# 8_0.net
KiCad netlist of a schematic drawn in Altium Designer
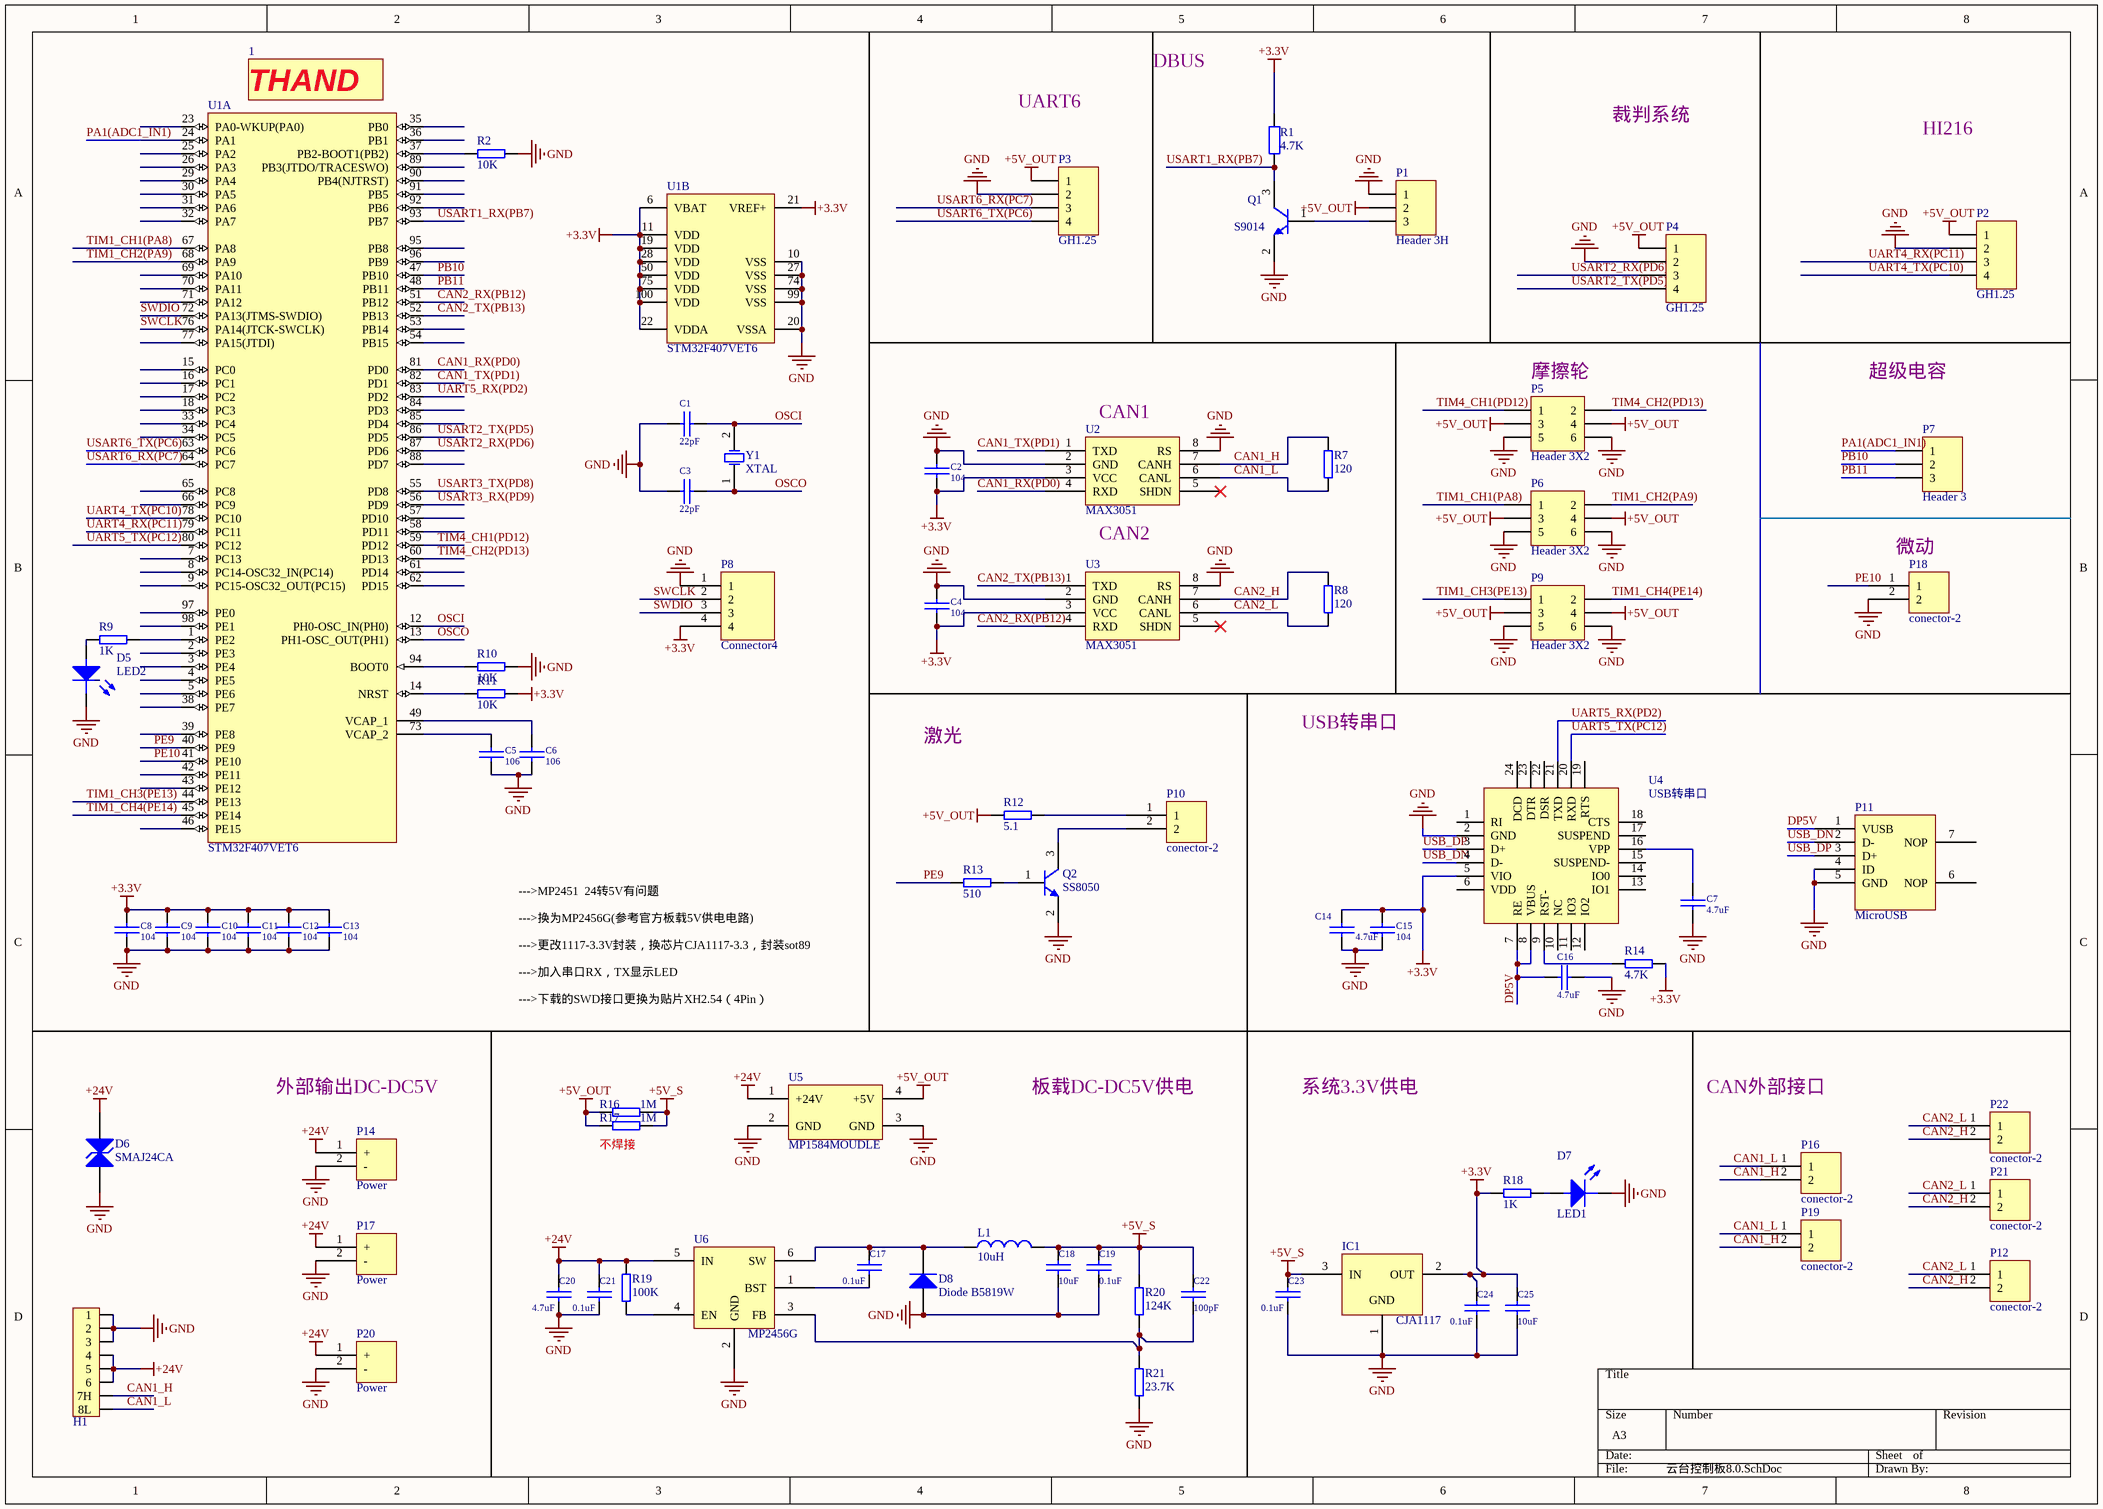
[diagram p0: 云台控制板8.0.SchDoc]

(export (version "E")
  (design (tool "Eeschema 10.0.6"))
  (components
    (comp (ref "1")
      (value "~")
      (footprint "THAND")
      (libsource (lib "G's Integrated_Library-System") (part "THAND"))
    )
    (comp (ref "C1")
      (value "22pF")
      (footprint "0805C")
      (description "Capacitor")
      (libsource (lib "Components") (part "CAP1"))
    )
    (comp (ref "C2")
      (value "104")
      (footprint "0805C")
      (description "Capacitor")
      (libsource (lib "Components") (part "CAP1"))
    )
    (comp (ref "C3")
      (value "22pF")
      (footprint "0805C")
      (description "Capacitor")
      (libsource (lib "Components") (part "CAP1"))
    )
    (comp (ref "C4")
      (value "104")
      (footprint "0805C")
      (description "Capacitor")
      (libsource (lib "Components") (part "CAP1"))
    )
    (comp (ref "C5")
      (value "106")
      (footprint "0805C")
      (description "Capacitor")
      (libsource (lib "Components") (part "CAP1"))
    )
    (comp (ref "C6")
      (value "106")
      (footprint "0805C")
      (description "Capacitor")
      (libsource (lib "Components") (part "CAP1"))
    )
    (comp (ref "C7")
      (value "4.7uF")
      (footprint "0805C")
      (description "Capacitor")
      (libsource (lib "Components") (part "CAP1"))
    )
    (comp (ref "C8")
      (value "104")
      (footprint "0805C")
      (description "Capacitor")
      (libsource (lib "Components") (part "CAP1"))
    )
    (comp (ref "C9")
      (value "104")
      (footprint "0805C")
      (description "Capacitor")
      (libsource (lib "Components") (part "CAP1"))
    )
    (comp (ref "C10")
      (value "104")
      (footprint "0805C")
      (description "Capacitor")
      (libsource (lib "Components") (part "CAP1"))
    )
    (comp (ref "C11")
      (value "104")
      (footprint "0805C")
      (description "Capacitor")
      (libsource (lib "Components") (part "CAP1"))
    )
    (comp (ref "C12")
      (value "104")
      (footprint "0805C")
      (description "Capacitor")
      (libsource (lib "Components") (part "CAP1"))
    )
    (comp (ref "C13")
      (value "104")
      (footprint "0805C")
      (description "Capacitor")
      (libsource (lib "Components") (part "CAP1"))
    )
    (comp (ref "C14")
      (value "4.7uF")
      (footprint "0805C")
      (description "Capacitor")
      (libsource (lib "Components") (part "CAP1"))
    )
    (comp (ref "C15")
      (value "104")
      (footprint "0805C")
      (description "Capacitor")
      (libsource (lib "Components") (part "CAP1"))
    )
    (comp (ref "C16")
      (value "4.7uF")
      (footprint "0805C")
      (description "Capacitor")
      (libsource (lib "Components") (part "CAP1"))
    )
    (comp (ref "C17")
      (value "0.1uF")
      (footprint "0805C")
      (description "Capacitor")
      (libsource (lib "Components") (part "CAP1"))
    )
    (comp (ref "C18")
      (value "10uF")
      (footprint "1206C")
      (description "Capacitor")
      (libsource (lib "Components") (part "CAP1"))
    )
    (comp (ref "C19")
      (value "0.1uF")
      (footprint "0805C")
      (description "Capacitor")
      (libsource (lib "Components") (part "CAP1"))
    )
    (comp (ref "C20")
      (value "4.7uF")
      (footprint "1206C")
      (description "Capacitor")
      (libsource (lib "Components") (part "CAP1"))
    )
    (comp (ref "C21")
      (value "0.1uF")
      (footprint "0805C")
      (description "Capacitor")
      (libsource (lib "Components") (part "CAP1"))
    )
    (comp (ref "C22")
      (value "100pF")
      (footprint "0805C")
      (description "Capacitor")
      (libsource (lib "Components") (part "CAP1"))
    )
    (comp (ref "C23")
      (value "0.1uF")
      (footprint "0805C")
      (description "Capacitor")
      (libsource (lib "Components") (part "CAP1"))
    )
    (comp (ref "C24")
      (value "0.1uF")
      (footprint "0805C")
      (description "Capacitor")
      (libsource (lib "Components") (part "CAP1"))
    )
    (comp (ref "C25")
      (value "10uF")
      (footprint "1206C")
      (description "Capacitor")
      (libsource (lib "Components") (part "CAP1"))
    )
    (comp (ref "D5")
      (value "LED2")
      (footprint "0805D")
      (description "Typical RED GaAs LED")
      (fields (field (name "PUBLISHER") "Altium Limited"))
      (libsource (lib "Components") (part "LED1"))
    )
    (comp (ref "D6")
      (value "SMAJ24CA")
      (footprint "SMA(DO-214AC)")
      (description "Diode TVS 双向")
      (fields (field (name "PUBLISHER") "Altium Limited"))
      (libsource (lib "Roxin_lib") (part "Diode TVS Bi"))
    )
    (comp (ref "D7")
      (value "LED1")
      (footprint "0805D")
      (description "Typical RED GaAs LED")
      (fields (field (name "PUBLISHER") "Altium Limited"))
      (libsource (lib "Components") (part "LED1"))
    )
    (comp (ref "D8")
      (value "Diode B5819W")
      (footprint "SOD-123")
      (description "1 Amp Fast Recovery Rectifier")
      (fields (field (name "PUBLISHER") "Altium Limited"))
      (libsource (lib "Roxin_lib") (part "Diode B5819W"))
    )
    (comp (ref "H1")
      (value "云台电机8P")
      (footprint "云台电机8P")
      (libsource (lib "IRS21867+SIR662DP") (part "云台电机8P"))
    )
    (comp (ref "IC1")
      (value "CJA1117")
      (footprint "SOT89 - duplicate")
      (libsource (lib "Roxin_lib") (part "CJA1117"))
    )
    (comp (ref "L1")
      (value "10uH")
      (footprint "SMDRH63")
      (description "Inductor")
      (fields (field (name "PUBLISHER") "Altium Limited"))
      (libsource (lib "Roxin_lib") (part "Inductor"))
    )
    (comp (ref "P1")
      (value "Header 3H")
      (footprint "HDR1X3H")
      (description "Header, 3-Pin, Right Angle")
      (fields (field (name "PUBLISHER") "Altium Limited"))
      (libsource (lib "Miscellaneous Connectors") (part "Header 3H"))
    )
    (comp (ref "P2")
      (value "GH1.25")
      (footprint "GH1.25_4P")
      (description "Header, 4-Pin")
      (fields (field (name "PUBLISHER") "Altium Limited"))
      (libsource (lib "主控V1") (part "Header 4"))
    )
    (comp (ref "P3")
      (value "GH1.25")
      (footprint "GH1.25_4P")
      (description "Header, 4-Pin")
      (fields (field (name "PUBLISHER") "Altium Limited"))
      (libsource (lib "主控V1") (part "Header 4"))
    )
    (comp (ref "P4")
      (value "GH1.25")
      (footprint "GH1.25_4P")
      (description "Header, 4-Pin")
      (fields (field (name "PUBLISHER") "Altium Limited"))
      (libsource (lib "主控V1") (part "Header 4"))
    )
    (comp (ref "P5")
      (value "Header 3X2")
      (footprint "HDR2X3")
      (description "Header, 3-Pin, Dual row")
      (fields (field (name "PUBLISHER") "Altium Limited"))
      (libsource (lib "Miscellaneous Connectors") (part "Header 3X2"))
    )
    (comp (ref "P6")
      (value "Header 3X2")
      (footprint "HDR2X3")
      (description "Header, 3-Pin, Dual row")
      (fields (field (name "PUBLISHER") "Altium Limited"))
      (libsource (lib "Miscellaneous Connectors") (part "Header 3X2"))
    )
    (comp (ref "P7")
      (value "Header 3")
      (footprint "HDR1X3")
      (description "Header, 3-Pin")
      (fields (field (name "PUBLISHER") "Altium Limited"))
      (libsource (lib "Miscellaneous Connectors") (part "Header 3"))
    )
    (comp (ref "P8")
      (value "Connector4")
      (footprint "XH2.54-4P")
      (description "白色插头母头")
      (libsource (lib "mylib") (part "Connector4"))
    )
    (comp (ref "P9")
      (value "Header 3X2")
      (footprint "HDR2X3")
      (description "Header, 3-Pin, Dual row")
      (fields (field (name "PUBLISHER") "Altium Limited"))
      (libsource (lib "Miscellaneous Connectors") (part "Header 3X2"))
    )
    (comp (ref "P10")
      (value "conector-2")
      (footprint "GH1.25-2P")
      (libsource (lib "Roxin_lib") (part "conector-2"))
    )
    (comp (ref "P11") (value "MicroUSB") (footprint "Micro-USB沉板") (libsource (lib "USB") (part "MicroUSB")))
    (comp (ref "P12")
      (value "conector-2")
      (footprint "GH1.25-2P")
      (libsource (lib "Roxin_lib") (part "conector-2"))
    )
    (comp (ref "P14") (value "Power") (footprint "XT30") (libsource (lib "云台控制板3.0") (part "Power")))
    (comp (ref "P16")
      (value "conector-2")
      (footprint "GH1.25-2P")
      (libsource (lib "Roxin_lib") (part "conector-2"))
    )
    (comp (ref "P17") (value "Power") (footprint "XT30") (libsource (lib "云台控制板3.0") (part "Power")))
    (comp (ref "P18")
      (value "conector-2")
      (footprint "GH1.25-2P")
      (libsource (lib "Roxin_lib") (part "conector-2"))
    )
    (comp (ref "P19")
      (value "conector-2")
      (footprint "GH1.25-2P")
      (libsource (lib "Roxin_lib") (part "conector-2"))
    )
    (comp (ref "P20") (value "Power") (footprint "XT30") (libsource (lib "Roxin_lib") (part "Power")))
    (comp (ref "P21")
      (value "conector-2")
      (footprint "GH1.25-2P")
      (libsource (lib "Roxin_lib") (part "conector-2"))
    )
    (comp (ref "P22")
      (value "conector-2")
      (footprint "GH1.25-2P")
      (libsource (lib "Roxin_lib") (part "conector-2"))
    )
    (comp (ref "Q1")
      (value "S9014")
      (footprint "SOT-23")
      (description "NPN贴片三极管")
      (fields (field (name "PUBLISHER") "Altium Limited"))
      (libsource (lib "主控V1") (part "SS8050"))
    )
    (comp (ref "Q2")
      (value "SS8050")
      (footprint "SOT-23")
      (description "NPN贴片三极管")
      (fields (field (name "PUBLISHER") "Altium Limited"))
      (libsource (lib "主控V1") (part "SS8050"))
    )
    (comp (ref "R1")
      (value "4.7K")
      (footprint "R0805")
      (description "Resistor")
      (fields (field (name "Comment") "Res2") (field (name "PUBLISHER") "Altium Limited"))
      (libsource (lib "Roxin_lib") (part "Res2"))
    )
    (comp (ref "R2")
      (value "10K")
      (footprint "0805R")
      (description "Resistance")
      (libsource (lib "Components") (part "RES"))
    )
    (comp (ref "R7")
      (value "120")
      (footprint "0805R")
      (description "Resistance")
      (libsource (lib "Components") (part "RES"))
    )
    (comp (ref "R8")
      (value "120")
      (footprint "0805R")
      (description "Resistance")
      (libsource (lib "Components") (part "RES"))
    )
    (comp (ref "R9")
      (value "1K")
      (footprint "0805R")
      (description "Resistance")
      (libsource (lib "Components") (part "RES"))
    )
    (comp (ref "R10")
      (value "10K")
      (footprint "0805R")
      (description "Resistance")
      (libsource (lib "Components") (part "RES"))
    )
    (comp (ref "R11")
      (value "10K")
      (footprint "0805R")
      (description "Resistance")
      (libsource (lib "Components") (part "RES"))
    )
    (comp (ref "R12")
      (value "5.1")
      (footprint "0805R")
      (description "Resistance")
      (libsource (lib "Components") (part "RES"))
    )
    (comp (ref "R13")
      (value "510")
      (footprint "0805R")
      (description "Resistance")
      (libsource (lib "Components") (part "RES"))
    )
    (comp (ref "R14")
      (value "4.7K")
      (footprint "0805R")
      (description "Resistance")
      (libsource (lib "Components") (part "RES"))
    )
    (comp (ref "R16")
      (value "1M")
      (footprint "0805R")
      (description "Resistance")
      (libsource (lib "Components") (part "RES"))
    )
    (comp (ref "R17")
      (value "1M")
      (footprint "0805R")
      (description "Resistance")
      (libsource (lib "Components") (part "RES"))
    )
    (comp (ref "R18")
      (value "1K")
      (footprint "0805R")
      (description "Resistance")
      (libsource (lib "Components") (part "RES"))
    )
    (comp (ref "R19")
      (value "100K")
      (footprint "0805R")
      (description "Resistance")
      (libsource (lib "Components") (part "RES"))
    )
    (comp (ref "R20")
      (value "124K")
      (footprint "0805R")
      (description "Resistance")
      (libsource (lib "Components") (part "RES"))
    )
    (comp (ref "R21")
      (value "23.7K")
      (footprint "0805R")
      (description "Resistance")
      (libsource (lib "Components") (part "RES"))
    )
    (comp (ref "U1")
      (value "STM32F407VET6")
      (footprint "STM-LQFP100_N")
      (fields (field (name "MANUFACTURER") "STMicroelectronics"))
      (libsource (lib "STMicroelectronics STM32 F4") (part "STM32F407VET6"))
    )
    (comp (ref "U2") (value "MAX3051") (footprint "SOIC8") (libsource (lib "PTZ") (part "MAX3051")))
    (comp (ref "U3") (value "MAX3051") (footprint "SOIC8") (libsource (lib "PTZ") (part "MAX3051")))
    (comp (ref "U4") (value "USB转串口") (footprint "CP2102") (libsource (lib "mylib") (part "CP2102")))
    (comp (ref "U5")
      (value "MP1584MOUDLE")
      (footprint "24-5VMP1584MOUDLE")
      (libsource (lib "Roxin_lib") (part "24-5VMP1584MOUDLE"))
    )
    (comp (ref "U6") (value "MP2456G") (footprint "SOT23-6") (libsource (lib "Roxin_lib") (part "MP2456G")))
    (comp (ref "Y1")
      (value "XTAL")
      (footprint "JZ")
      (description "Crystal Oscillator")
      (fields (field (name "PUBLISHER") "Altium Limited"))
      (libsource (lib "Roxin_lib") (part "XTAL"))
    )
  )
  (nets
    (net (code "1") (name "+3.3V") (class "Default")
      (node (ref "C10") (pin "1") (pinfunction "1_1") (pintype "passive"))
      (node (ref "C11") (pin "1") (pinfunction "1_1") (pintype "passive"))
      (node (ref "C12") (pin "1") (pinfunction "1_1") (pintype "passive"))
      (node (ref "C13") (pin "1") (pinfunction "1_1") (pintype "passive"))
      (node (ref "C14") (pin "1") (pinfunction "1_1") (pintype "passive"))
      (node (ref "C15") (pin "2") (pinfunction "2_2") (pintype "passive"))
      (node (ref "C2") (pin "2") (pinfunction "2_2") (pintype "passive"))
      (node (ref "C24") (pin "1") (pinfunction "1_1") (pintype "passive"))
      (node (ref "C25") (pin "1") (pinfunction "1_1") (pintype "passive"))
      (node (ref "C4") (pin "2") (pinfunction "2_2") (pintype "passive"))
      (node (ref "C8") (pin "1") (pinfunction "1_1") (pintype "passive"))
      (node (ref "C9") (pin "1") (pinfunction "1_1") (pintype "passive"))
      (node (ref "IC1") (pin "2") (pinfunction "OUT_2") (pintype "passive"))
      (node (ref "P8") (pin "4") (pinfunction "4_4") (pintype "passive"))
      (node (ref "R1") (pin "2") (pinfunction "2_2") (pintype "passive"))
      (node (ref "R11") (pin "2") (pinfunction "2_2") (pintype "passive"))
      (node (ref "R14") (pin "2") (pinfunction "2_2") (pintype "passive"))
      (node (ref "R18") (pin "1") (pinfunction "1_1") (pintype "passive"))
      (node (ref "U1") (pin "100") (pinfunction "VDD_100") (pintype "power_in"))
      (node (ref "U1") (pin "11") (pinfunction "VDD_11") (pintype "power_in"))
      (node (ref "U1") (pin "19") (pinfunction "VDD_19") (pintype "power_in"))
      (node (ref "U1") (pin "21") (pinfunction "VREF+_21") (pintype "power_in"))
      (node (ref "U1") (pin "22") (pinfunction "VDDA_22") (pintype "power_in"))
      (node (ref "U1") (pin "28") (pinfunction "VDD_28") (pintype "power_in"))
      (node (ref "U1") (pin "50") (pinfunction "VDD_50") (pintype "power_in"))
      (node (ref "U1") (pin "6") (pinfunction "VBAT_6") (pintype "power_in"))
      (node (ref "U1") (pin "75") (pinfunction "VDD_75") (pintype "power_in"))
      (node (ref "U2") (pin "3") (pinfunction "VCC_3") (pintype "passive"))
      (node (ref "U3") (pin "3") (pinfunction "VCC_3") (pintype "passive"))
      (node (ref "U4") (pin "5") (pinfunction "VIO_5") (pintype "passive"))
    )
    (net (code "2") (name "+5V_OUT") (class "Default")
      (node (ref "P1") (pin "2") (pinfunction "2_2") (pintype "passive"))
      (node (ref "P2") (pin "1") (pinfunction "1_1") (pintype "passive"))
      (node (ref "P3") (pin "1") (pinfunction "1_1") (pintype "passive"))
      (node (ref "P4") (pin "1") (pinfunction "1_1") (pintype "passive"))
      (node (ref "P5") (pin "3") (pinfunction "3_3") (pintype "passive"))
      (node (ref "P5") (pin "4") (pinfunction "4_4") (pintype "passive"))
      (node (ref "P6") (pin "3") (pinfunction "3_3") (pintype "passive"))
      (node (ref "P6") (pin "4") (pinfunction "4_4") (pintype "passive"))
      (node (ref "P9") (pin "3") (pinfunction "3_3") (pintype "passive"))
      (node (ref "P9") (pin "4") (pinfunction "4_4") (pintype "passive"))
      (node (ref "R12") (pin "1") (pinfunction "1_1") (pintype "passive"))
      (node (ref "R16") (pin "1") (pinfunction "1_1") (pintype "passive"))
      (node (ref "R17") (pin "1") (pinfunction "1_1") (pintype "passive"))
      (node (ref "U5") (pin "4") (pinfunction "+5V_4") (pintype "passive"))
    )
    (net (code "3") (name "+5V_S") (class "Default")
      (node (ref "C18") (pin "1") (pinfunction "1_1") (pintype "passive"))
      (node (ref "C19") (pin "1") (pinfunction "1_1") (pintype "passive"))
      (node (ref "C22") (pin "1") (pinfunction "1_1") (pintype "passive"))
      (node (ref "C23") (pin "1") (pinfunction "1_1") (pintype "passive"))
      (node (ref "IC1") (pin "3") (pinfunction "IN_3") (pintype "passive"))
      (node (ref "L1") (pin "2") (pinfunction "2_2") (pintype "passive"))
      (node (ref "R16") (pin "2") (pinfunction "2_2") (pintype "passive"))
      (node (ref "R17") (pin "2") (pinfunction "2_2") (pintype "passive"))
      (node (ref "R20") (pin "2") (pinfunction "2_2") (pintype "passive"))
    )
    (net (code "4") (name "+24V") (class "Default")
      (node (ref "C20") (pin "1") (pinfunction "1_1") (pintype "passive"))
      (node (ref "C21") (pin "1") (pinfunction "1_1") (pintype "passive"))
      (node (ref "D6") (pin "2") (pinfunction "K_2") (pintype "passive"))
      (node (ref "H1") (pin "4") (pinfunction "4_4") (pintype "passive"))
      (node (ref "H1") (pin "5") (pinfunction "5_5") (pintype "passive"))
      (node (ref "H1") (pin "6") (pinfunction "6_6") (pintype "passive"))
      (node (ref "P14") (pin "1") (pinfunction "+_1") (pintype "passive"))
      (node (ref "P17") (pin "1") (pinfunction "+_1") (pintype "passive"))
      (node (ref "P20") (pin "1") (pinfunction "+_1") (pintype "passive"))
      (node (ref "R19") (pin "2") (pinfunction "2_2") (pintype "passive"))
      (node (ref "U5") (pin "1") (pinfunction "+24V_1") (pintype "passive"))
      (node (ref "U6") (pin "5") (pinfunction "IN_5") (pintype "passive"))
    )
    (net (code "5") (name "/CAN1_H") (class "Default")
      (node (ref "H1") (pin "7") (pinfunction "7H_7") (pintype "passive"))
      (node (ref "P16") (pin "2") (pinfunction "2_2") (pintype "passive"))
      (node (ref "P19") (pin "2") (pinfunction "2_2") (pintype "passive"))
      (node (ref "R7") (pin "2") (pinfunction "2_2") (pintype "passive"))
      (node (ref "U2") (pin "7") (pinfunction "CANH_7") (pintype "passive"))
    )
    (net (code "6") (name "/CAN1_L") (class "Default")
      (node (ref "H1") (pin "8") (pinfunction "8L_8") (pintype "passive"))
      (node (ref "P16") (pin "1") (pinfunction "1_1") (pintype "passive"))
      (node (ref "P19") (pin "1") (pinfunction "1_1") (pintype "passive"))
      (node (ref "R7") (pin "1") (pinfunction "1_1") (pintype "passive"))
      (node (ref "U2") (pin "6") (pinfunction "CANL_6") (pintype "passive"))
    )
    (net (code "7") (name "/CAN1_RX(PD0)") (class "Default")
      (node (ref "U1") (pin "81") (pinfunction "PD0_81") (pintype "bidirectional"))
      (node (ref "U2") (pin "4") (pinfunction "RXD_4") (pintype "passive"))
    )
    (net (code "8") (name "/CAN1_TX(PD1)") (class "Default")
      (node (ref "U1") (pin "82") (pinfunction "PD1_82") (pintype "bidirectional"))
      (node (ref "U2") (pin "1") (pinfunction "TXD_1") (pintype "passive"))
    )
    (net (code "9") (name "/CAN2_H") (class "Default")
      (node (ref "P12") (pin "2") (pinfunction "2_2") (pintype "passive"))
      (node (ref "P21") (pin "2") (pinfunction "2_2") (pintype "passive"))
      (node (ref "P22") (pin "2") (pinfunction "2_2") (pintype "passive"))
      (node (ref "R8") (pin "2") (pinfunction "2_2") (pintype "passive"))
      (node (ref "U3") (pin "7") (pinfunction "CANH_7") (pintype "passive"))
    )
    (net (code "10") (name "/CAN2_L") (class "Default")
      (node (ref "P12") (pin "1") (pinfunction "1_1") (pintype "passive"))
      (node (ref "P21") (pin "1") (pinfunction "1_1") (pintype "passive"))
      (node (ref "P22") (pin "1") (pinfunction "1_1") (pintype "passive"))
      (node (ref "R8") (pin "1") (pinfunction "1_1") (pintype "passive"))
      (node (ref "U3") (pin "6") (pinfunction "CANL_6") (pintype "passive"))
    )
    (net (code "11") (name "/CAN2_RX(PB12)") (class "Default")
      (node (ref "U1") (pin "51") (pinfunction "PB12_51") (pintype "bidirectional"))
      (node (ref "U3") (pin "4") (pinfunction "RXD_4") (pintype "passive"))
    )
    (net (code "12") (name "/CAN2_TX(PB13)") (class "Default")
      (node (ref "U1") (pin "52") (pinfunction "PB13_52") (pintype "bidirectional"))
      (node (ref "U3") (pin "1") (pinfunction "TXD_1") (pintype "passive"))
    )
    (net (code "13") (name "/DP5V") (class "Default")
      (node (ref "C16") (pin "1") (pinfunction "1_1") (pintype "passive"))
      (node (ref "P11") (pin "1") (pinfunction "VUSB_1") (pintype "passive"))
      (node (ref "U4") (pin "7") (pinfunction "RE_7") (pintype "passive"))
      (node (ref "U4") (pin "8") (pinfunction "VBUS_8") (pintype "passive"))
    )
    (net (code "14") (name "/OSCI") (class "Default")
      (node (ref "C1") (pin "2") (pinfunction "2_2") (pintype "passive"))
      (node (ref "U1") (pin "12") (pinfunction "PH0-OSC_IN(PH0)_12") (pintype "bidirectional"))
      (node (ref "Y1") (pin "2") (pinfunction "OSC2_2") (pintype "passive"))
    )
    (net (code "15") (name "/OSCO") (class "Default")
      (node (ref "C3") (pin "2") (pinfunction "2_2") (pintype "passive"))
      (node (ref "U1") (pin "13") (pinfunction "PH1-OSC_OUT(PH1)_13") (pintype "bidirectional"))
      (node (ref "Y1") (pin "1") (pinfunction "OSC1_1") (pintype "passive"))
    )
    (net (code "16") (name "/PA1(ADC1_IN1)") (class "Default")
      (node (ref "P7") (pin "1") (pinfunction "1_1") (pintype "passive"))
      (node (ref "U1") (pin "24") (pinfunction "PA1_24") (pintype "bidirectional"))
    )
    (net (code "17") (name "/PB10") (class "Default")
      (node (ref "P7") (pin "2") (pinfunction "2_2") (pintype "passive"))
      (node (ref "U1") (pin "47") (pinfunction "PB10_47") (pintype "bidirectional"))
    )
    (net (code "18") (name "/PB11") (class "Default")
      (node (ref "P7") (pin "3") (pinfunction "3_3") (pintype "passive"))
      (node (ref "U1") (pin "48") (pinfunction "PB11_48") (pintype "bidirectional"))
    )
    (net (code "19") (name "/PE9") (class "Default")
      (node (ref "R13") (pin "1") (pinfunction "1_1") (pintype "passive"))
      (node (ref "U1") (pin "40") (pinfunction "PE9_40") (pintype "bidirectional"))
    )
    (net (code "20") (name "/PE10") (class "Default")
      (node (ref "P18") (pin "1") (pinfunction "1_1") (pintype "passive"))
      (node (ref "U1") (pin "41") (pinfunction "PE10_41") (pintype "bidirectional"))
    )
    (net (code "21") (name "/SWCLK") (class "Default")
      (node (ref "P8") (pin "2") (pinfunction "2_2") (pintype "passive"))
      (node (ref "U1") (pin "76") (pinfunction "PA14(JTCK-SWCLK)_76") (pintype "bidirectional"))
    )
    (net (code "22") (name "/SWDIO") (class "Default")
      (node (ref "P8") (pin "3") (pinfunction "3_3") (pintype "passive"))
      (node (ref "U1") (pin "72") (pinfunction "PA13(JTMS-SWDIO)_72") (pintype "bidirectional"))
    )
    (net (code "23") (name "/TIM1_CH1(PA8)") (class "Default")
      (node (ref "P6") (pin "1") (pinfunction "1_1") (pintype "passive"))
      (node (ref "U1") (pin "67") (pinfunction "PA8_67") (pintype "bidirectional"))
    )
    (net (code "24") (name "/TIM1_CH2(PA9)") (class "Default")
      (node (ref "P6") (pin "2") (pinfunction "2_2") (pintype "passive"))
      (node (ref "U1") (pin "68") (pinfunction "PA9_68") (pintype "bidirectional"))
    )
    (net (code "25") (name "/TIM1_CH3(PE13)") (class "Default")
      (node (ref "P9") (pin "1") (pinfunction "1_1") (pintype "passive"))
      (node (ref "U1") (pin "44") (pinfunction "PE13_44") (pintype "bidirectional"))
    )
    (net (code "26") (name "/TIM1_CH4(PE14)") (class "Default")
      (node (ref "P9") (pin "2") (pinfunction "2_2") (pintype "passive"))
      (node (ref "U1") (pin "45") (pinfunction "PE14_45") (pintype "bidirectional"))
    )
    (net (code "27") (name "/TIM4_CH1(PD12)") (class "Default")
      (node (ref "P5") (pin "1") (pinfunction "1_1") (pintype "passive"))
      (node (ref "U1") (pin "59") (pinfunction "PD12_59") (pintype "bidirectional"))
    )
    (net (code "28") (name "/TIM4_CH2(PD13)") (class "Default")
      (node (ref "P5") (pin "2") (pinfunction "2_2") (pintype "passive"))
      (node (ref "U1") (pin "60") (pinfunction "PD13_60") (pintype "bidirectional"))
    )
    (net (code "29") (name "/UART4_RX(PC11)") (class "Default")
      (node (ref "P2") (pin "3") (pinfunction "3_3") (pintype "passive"))
      (node (ref "U1") (pin "79") (pinfunction "PC11_79") (pintype "bidirectional"))
    )
    (net (code "30") (name "/UART4_TX(PC10)") (class "Default")
      (node (ref "P2") (pin "4") (pinfunction "4_4") (pintype "passive"))
      (node (ref "U1") (pin "78") (pinfunction "PC10_78") (pintype "bidirectional"))
    )
    (net (code "31") (name "/UART5_RX(PD2)") (class "Default")
      (node (ref "U1") (pin "83") (pinfunction "PD2_83") (pintype "bidirectional"))
      (node (ref "U4") (pin "21") (pinfunction "TXD_21") (pintype "passive"))
    )
    (net (code "32") (name "/UART5_TX(PC12)") (class "Default")
      (node (ref "U1") (pin "80") (pinfunction "PC12_80") (pintype "bidirectional"))
      (node (ref "U4") (pin "20") (pinfunction "RXD_20") (pintype "passive"))
    )
    (net (code "33") (name "/USART1_RX(PB7)") (class "Default")
      (node (ref "Q1") (pin "3") (pinfunction "C_3") (pintype "passive"))
      (node (ref "R1") (pin "1") (pinfunction "1_1") (pintype "passive"))
      (node (ref "U1") (pin "93") (pinfunction "PB7_93") (pintype "bidirectional"))
    )
    (net (code "34") (name "/USART2_RX(PD6)") (class "Default")
      (node (ref "P4") (pin "3") (pinfunction "3_3") (pintype "passive"))
      (node (ref "U1") (pin "87") (pinfunction "PD6_87") (pintype "bidirectional"))
    )
    (net (code "35") (name "/USART2_TX(PD5)") (class "Default")
      (node (ref "P4") (pin "4") (pinfunction "4_4") (pintype "passive"))
      (node (ref "U1") (pin "86") (pinfunction "PD5_86") (pintype "bidirectional"))
    )
    (net (code "36") (name "/USART3_RX(PD9)") (class "Default")
      (node (ref "U1") (pin "56") (pinfunction "PD9_56") (pintype "bidirectional"))
    )
    (net (code "37") (name "/USART3_TX(PD8)") (class "Default")
      (node (ref "U1") (pin "55") (pinfunction "PD8_55") (pintype "bidirectional"))
    )
    (net (code "38") (name "/USART6_RX(PC7)") (class "Default")
      (node (ref "P3") (pin "3") (pinfunction "3_3") (pintype "passive"))
      (node (ref "U1") (pin "64") (pinfunction "PC7_64") (pintype "bidirectional"))
    )
    (net (code "39") (name "/USART6_TX(PC6)") (class "Default")
      (node (ref "P3") (pin "4") (pinfunction "4_4") (pintype "passive"))
      (node (ref "U1") (pin "63") (pinfunction "PC6_63") (pintype "bidirectional"))
    )
    (net (code "40") (name "/USB_DN") (class "Default")
      (node (ref "P11") (pin "2") (pinfunction "D-_2") (pintype "passive"))
      (node (ref "U4") (pin "4") (pinfunction "D-_4") (pintype "passive"))
    )
    (net (code "41") (name "/USB_DP") (class "Default")
      (node (ref "P11") (pin "3") (pinfunction "D+_3") (pintype "passive"))
      (node (ref "U4") (pin "3") (pinfunction "D+_3") (pintype "passive"))
    )
    (net (code "42") (name "GND") (class "Default")
      (node (ref "C1") (pin "1") (pinfunction "1_1") (pintype "passive"))
      (node (ref "C10") (pin "2") (pinfunction "2_2") (pintype "passive"))
      (node (ref "C11") (pin "2") (pinfunction "2_2") (pintype "passive"))
      (node (ref "C12") (pin "2") (pinfunction "2_2") (pintype "passive"))
      (node (ref "C13") (pin "2") (pinfunction "2_2") (pintype "passive"))
      (node (ref "C14") (pin "2") (pinfunction "2_2") (pintype "passive"))
      (node (ref "C15") (pin "1") (pinfunction "1_1") (pintype "passive"))
      (node (ref "C16") (pin "2") (pinfunction "2_2") (pintype "passive"))
      (node (ref "C18") (pin "2") (pinfunction "2_2") (pintype "passive"))
      (node (ref "C19") (pin "2") (pinfunction "2_2") (pintype "passive"))
      (node (ref "C2") (pin "1") (pinfunction "1_1") (pintype "passive"))
      (node (ref "C20") (pin "2") (pinfunction "2_2") (pintype "passive"))
      (node (ref "C21") (pin "2") (pinfunction "2_2") (pintype "passive"))
      (node (ref "C23") (pin "2") (pinfunction "2_2") (pintype "passive"))
      (node (ref "C24") (pin "2") (pinfunction "2_2") (pintype "passive"))
      (node (ref "C25") (pin "2") (pinfunction "2_2") (pintype "passive"))
      (node (ref "C3") (pin "1") (pinfunction "1_1") (pintype "passive"))
      (node (ref "C4") (pin "1") (pinfunction "1_1") (pintype "passive"))
      (node (ref "C5") (pin "2") (pinfunction "2_2") (pintype "passive"))
      (node (ref "C6") (pin "2") (pinfunction "2_2") (pintype "passive"))
      (node (ref "C7") (pin "1") (pinfunction "1_1") (pintype "passive"))
      (node (ref "C8") (pin "2") (pinfunction "2_2") (pintype "passive"))
      (node (ref "C9") (pin "2") (pinfunction "2_2") (pintype "passive"))
      (node (ref "D5") (pin "2") (pinfunction "K_2") (pintype "passive"))
      (node (ref "D6") (pin "1") (pinfunction "A_1") (pintype "passive"))
      (node (ref "D7") (pin "2") (pinfunction "K_2") (pintype "passive"))
      (node (ref "D8") (pin "1") (pinfunction "A_1") (pintype "passive"))
      (node (ref "H1") (pin "1") (pinfunction "1_1") (pintype "passive"))
      (node (ref "H1") (pin "2") (pinfunction "2_2") (pintype "passive"))
      (node (ref "H1") (pin "3") (pinfunction "3_3") (pintype "passive"))
      (node (ref "IC1") (pin "1") (pinfunction "GND_1") (pintype "passive"))
      (node (ref "P1") (pin "1") (pinfunction "1_1") (pintype "passive"))
      (node (ref "P11") (pin "4") (pinfunction "ID_4") (pintype "passive"))
      (node (ref "P11") (pin "5") (pinfunction "GND_5") (pintype "passive"))
      (node (ref "P14") (pin "2") (pinfunction "-_2") (pintype "passive"))
      (node (ref "P17") (pin "2") (pinfunction "-_2") (pintype "passive"))
      (node (ref "P18") (pin "2") (pinfunction "2_2") (pintype "passive"))
      (node (ref "P2") (pin "2") (pinfunction "2_2") (pintype "passive"))
      (node (ref "P20") (pin "2") (pinfunction "-_2") (pintype "passive"))
      (node (ref "P3") (pin "2") (pinfunction "2_2") (pintype "passive"))
      (node (ref "P4") (pin "2") (pinfunction "2_2") (pintype "passive"))
      (node (ref "P5") (pin "5") (pinfunction "5_5") (pintype "passive"))
      (node (ref "P5") (pin "6") (pinfunction "6_6") (pintype "passive"))
      (node (ref "P6") (pin "5") (pinfunction "5_5") (pintype "passive"))
      (node (ref "P6") (pin "6") (pinfunction "6_6") (pintype "passive"))
      (node (ref "P8") (pin "1") (pinfunction "1_1") (pintype "passive"))
      (node (ref "P9") (pin "5") (pinfunction "5_5") (pintype "passive"))
      (node (ref "P9") (pin "6") (pinfunction "6_6") (pintype "passive"))
      (node (ref "Q1") (pin "2") (pinfunction "E_2") (pintype "passive"))
      (node (ref "Q2") (pin "2") (pinfunction "E_2") (pintype "passive"))
      (node (ref "R10") (pin "2") (pinfunction "2_2") (pintype "passive"))
      (node (ref "R2") (pin "2") (pinfunction "2_2") (pintype "passive"))
      (node (ref "R21") (pin "1") (pinfunction "1_1") (pintype "passive"))
      (node (ref "U1") (pin "10") (pinfunction "VSS_10") (pintype "power_in"))
      (node (ref "U1") (pin "20") (pinfunction "VSSA_20") (pintype "power_in"))
      (node (ref "U1") (pin "27") (pinfunction "VSS_27") (pintype "power_in"))
      (node (ref "U1") (pin "74") (pinfunction "VSS_74") (pintype "power_in"))
      (node (ref "U1") (pin "99") (pinfunction "VSS_99") (pintype "power_in"))
      (node (ref "U2") (pin "2") (pinfunction "GND_2") (pintype "passive"))
      (node (ref "U2") (pin "8") (pinfunction "RS_8") (pintype "passive"))
      (node (ref "U3") (pin "2") (pinfunction "GND_2") (pintype "passive"))
      (node (ref "U3") (pin "8") (pinfunction "RS_8") (pintype "passive"))
      (node (ref "U4") (pin "2") (pinfunction "GND_2") (pintype "passive"))
      (node (ref "U5") (pin "2") (pinfunction "GND_2") (pintype "passive"))
      (node (ref "U5") (pin "3") (pinfunction "GND_3") (pintype "passive"))
      (node (ref "U6") (pin "2") (pinfunction "GND_2") (pintype "passive"))
    )
    (net (code "43") (name "Net-(D5-A)") (class "Default")
      (node (ref "D5") (pin "1") (pinfunction "A_1") (pintype "passive"))
      (node (ref "R9") (pin "2") (pinfunction "2_2") (pintype "passive"))
    )
    (net (code "44") (name "Net-(D7-A)") (class "Default")
      (node (ref "D7") (pin "1") (pinfunction "A_1") (pintype "passive"))
      (node (ref "R18") (pin "2") (pinfunction "2_2") (pintype "passive"))
    )
    (net (code "45") (name "Net-(D8-K)") (class "Default")
      (node (ref "C17") (pin "1") (pinfunction "1_1") (pintype "passive"))
      (node (ref "D8") (pin "2") (pinfunction "K_2") (pintype "passive"))
      (node (ref "L1") (pin "1") (pinfunction "1_1") (pintype "passive"))
      (node (ref "U6") (pin "6") (pinfunction "SW_6") (pintype "passive"))
    )
    (net (code "46") (name "Net-(P10-Pad1)") (class "Default")
      (node (ref "P10") (pin "1") (pinfunction "1_1") (pintype "passive"))
      (node (ref "R12") (pin "2") (pinfunction "2_2") (pintype "passive"))
    )
    (net (code "47") (name "Net-(Q1-B)") (class "Default")
      (node (ref "P1") (pin "3") (pinfunction "3_3") (pintype "passive"))
      (node (ref "Q1") (pin "1") (pinfunction "B_1") (pintype "passive"))
    )
    (net (code "48") (name "Net-(Q2-B)") (class "Default")
      (node (ref "Q2") (pin "1") (pinfunction "B_1") (pintype "passive"))
      (node (ref "R13") (pin "2") (pinfunction "2_2") (pintype "passive"))
    )
    (net (code "49") (name "Net-(Q2-C)") (class "Default")
      (node (ref "P10") (pin "2") (pinfunction "2_2") (pintype "passive"))
      (node (ref "Q2") (pin "3") (pinfunction "C_3") (pintype "passive"))
    )
    (net (code "50") (name "Net-(U1A-BOOT0)") (class "Default")
      (node (ref "R10") (pin "1") (pinfunction "1_1") (pintype "passive"))
      (node (ref "U1") (pin "94") (pinfunction "BOOT0_94") (pintype "input"))
    )
    (net (code "51") (name "Net-(U1A-NRST)") (class "Default")
      (node (ref "R11") (pin "1") (pinfunction "1_1") (pintype "passive"))
      (node (ref "U1") (pin "14") (pinfunction "NRST_14") (pintype "bidirectional"))
    )
    (net (code "52") (name "Net-(U1A-PB2-BOOT1(PB2))") (class "Default")
      (node (ref "R2") (pin "1") (pinfunction "1_1") (pintype "passive"))
      (node (ref "U1") (pin "37") (pinfunction "PB2-BOOT1(PB2)_37") (pintype "bidirectional"))
    )
    (net (code "53") (name "Net-(U1A-PE2)") (class "Default")
      (node (ref "R9") (pin "1") (pinfunction "1_1") (pintype "passive"))
      (node (ref "U1") (pin "1") (pinfunction "PE2_1") (pintype "bidirectional"))
    )
    (net (code "54") (name "Net-(U1A-VCAP_1)") (class "Default")
      (node (ref "C6") (pin "1") (pinfunction "1_1") (pintype "passive"))
      (node (ref "U1") (pin "49") (pinfunction "VCAP_1_49") (pintype "power_in"))
    )
    (net (code "55") (name "Net-(U1A-VCAP_2)") (class "Default")
      (node (ref "C5") (pin "1") (pinfunction "1_1") (pintype "passive"))
      (node (ref "U1") (pin "73") (pinfunction "VCAP_2_73") (pintype "power_in"))
    )
    (net (code "56") (name "Net-(U4-RST-)") (class "Default")
      (node (ref "R14") (pin "1") (pinfunction "1_1") (pintype "passive"))
      (node (ref "U4") (pin "9") (pinfunction "RST-_9") (pintype "passive"))
    )
    (net (code "57") (name "Net-(U4-VPP)") (class "Default")
      (node (ref "C7") (pin "2") (pinfunction "2_2") (pintype "passive"))
      (node (ref "U4") (pin "16") (pinfunction "VPP_16") (pintype "passive"))
    )
    (net (code "58") (name "Net-(U6-BST)") (class "Default")
      (node (ref "C17") (pin "2") (pinfunction "2_2") (pintype "passive"))
      (node (ref "U6") (pin "1") (pinfunction "BST_1") (pintype "passive"))
    )
    (net (code "59") (name "Net-(U6-EN)") (class "Default")
      (node (ref "R19") (pin "1") (pinfunction "1_1") (pintype "passive"))
      (node (ref "U6") (pin "4") (pinfunction "EN_4") (pintype "passive"))
    )
    (net (code "60") (name "Net-(U6-FB)") (class "Default")
      (node (ref "C22") (pin "2") (pinfunction "2_2") (pintype "passive"))
      (node (ref "R20") (pin "1") (pinfunction "1_1") (pintype "passive"))
      (node (ref "R21") (pin "2") (pinfunction "2_2") (pintype "passive"))
      (node (ref "U6") (pin "3") (pinfunction "FB_3") (pintype "passive"))
    )
    (net (code "61") (name "unconnected-(P11-NOP-Pad6)") (class "Default")
      (node (ref "P11") (pin "6") (pinfunction "NOP_6") (pintype "passive"))
    )
    (net (code "62") (name "unconnected-(P11-NOP-Pad7)") (class "Default")
      (node (ref "P11") (pin "7") (pinfunction "NOP_7") (pintype "passive"))
    )
    (net (code "63") (name "unconnected-(U1A-PA0-WKUP(PA0)-Pad23)") (class "Default")
      (node (ref "U1") (pin "23") (pinfunction "PA0-WKUP(PA0)_23") (pintype "bidirectional"))
    )
    (net (code "64") (name "unconnected-(U1A-PA2-Pad25)") (class "Default")
      (node (ref "U1") (pin "25") (pinfunction "PA2_25") (pintype "bidirectional"))
    )
    (net (code "65") (name "unconnected-(U1A-PA3-Pad26)") (class "Default")
      (node (ref "U1") (pin "26") (pinfunction "PA3_26") (pintype "bidirectional"))
    )
    (net (code "66") (name "unconnected-(U1A-PA4-Pad29)") (class "Default")
      (node (ref "U1") (pin "29") (pinfunction "PA4_29") (pintype "bidirectional"))
    )
    (net (code "67") (name "unconnected-(U1A-PA5-Pad30)") (class "Default")
      (node (ref "U1") (pin "30") (pinfunction "PA5_30") (pintype "bidirectional"))
    )
    (net (code "68") (name "unconnected-(U1A-PA6-Pad31)") (class "Default")
      (node (ref "U1") (pin "31") (pinfunction "PA6_31") (pintype "bidirectional"))
    )
    (net (code "69") (name "unconnected-(U1A-PA7-Pad32)") (class "Default")
      (node (ref "U1") (pin "32") (pinfunction "PA7_32") (pintype "bidirectional"))
    )
    (net (code "70") (name "unconnected-(U1A-PA10-Pad69)") (class "Default")
      (node (ref "U1") (pin "69") (pinfunction "PA10_69") (pintype "bidirectional"))
    )
    (net (code "71") (name "unconnected-(U1A-PA11-Pad70)") (class "Default")
      (node (ref "U1") (pin "70") (pinfunction "PA11_70") (pintype "bidirectional"))
    )
    (net (code "72") (name "unconnected-(U1A-PA12-Pad71)") (class "Default")
      (node (ref "U1") (pin "71") (pinfunction "PA12_71") (pintype "bidirectional"))
    )
    (net (code "73") (name "unconnected-(U1A-PA15(JTDI)-Pad77)") (class "Default")
      (node (ref "U1") (pin "77") (pinfunction "PA15(JTDI)_77") (pintype "bidirectional"))
    )
    (net (code "74") (name "unconnected-(U1A-PB0-Pad35)") (class "Default")
      (node (ref "U1") (pin "35") (pinfunction "PB0_35") (pintype "bidirectional"))
    )
    (net (code "75") (name "unconnected-(U1A-PB1-Pad36)") (class "Default")
      (node (ref "U1") (pin "36") (pinfunction "PB1_36") (pintype "bidirectional"))
    )
    (net (code "76") (name "unconnected-(U1A-PB3(JTDO{slash}TRACESWO)-Pad89)") (class "Default")
      (node (ref "U1") (pin "89") (pinfunction "PB3(JTDO/TRACESWO)_89") (pintype "bidirectional"))
    )
    (net (code "77") (name "unconnected-(U1A-PB4(NJTRST)-Pad90)") (class "Default")
      (node (ref "U1") (pin "90") (pinfunction "PB4(NJTRST)_90") (pintype "bidirectional"))
    )
    (net (code "78") (name "unconnected-(U1A-PB5-Pad91)") (class "Default")
      (node (ref "U1") (pin "91") (pinfunction "PB5_91") (pintype "bidirectional"))
    )
    (net (code "79") (name "unconnected-(U1A-PB6-Pad92)") (class "Default")
      (node (ref "U1") (pin "92") (pinfunction "PB6_92") (pintype "bidirectional"))
    )
    (net (code "80") (name "unconnected-(U1A-PB8-Pad95)") (class "Default")
      (node (ref "U1") (pin "95") (pinfunction "PB8_95") (pintype "bidirectional"))
    )
    (net (code "81") (name "unconnected-(U1A-PB9-Pad96)") (class "Default")
      (node (ref "U1") (pin "96") (pinfunction "PB9_96") (pintype "bidirectional"))
    )
    (net (code "82") (name "unconnected-(U1A-PB14-Pad53)") (class "Default")
      (node (ref "U1") (pin "53") (pinfunction "PB14_53") (pintype "bidirectional"))
    )
    (net (code "83") (name "unconnected-(U1A-PB15-Pad54)") (class "Default")
      (node (ref "U1") (pin "54") (pinfunction "PB15_54") (pintype "bidirectional"))
    )
    (net (code "84") (name "unconnected-(U1A-PC0-Pad15)") (class "Default")
      (node (ref "U1") (pin "15") (pinfunction "PC0_15") (pintype "bidirectional"))
    )
    (net (code "85") (name "unconnected-(U1A-PC1-Pad16)") (class "Default")
      (node (ref "U1") (pin "16") (pinfunction "PC1_16") (pintype "bidirectional"))
    )
    (net (code "86") (name "unconnected-(U1A-PC2-Pad17)") (class "Default")
      (node (ref "U1") (pin "17") (pinfunction "PC2_17") (pintype "bidirectional"))
    )
    (net (code "87") (name "unconnected-(U1A-PC3-Pad18)") (class "Default")
      (node (ref "U1") (pin "18") (pinfunction "PC3_18") (pintype "bidirectional"))
    )
    (net (code "88") (name "unconnected-(U1A-PC4-Pad33)") (class "Default")
      (node (ref "U1") (pin "33") (pinfunction "PC4_33") (pintype "bidirectional"))
    )
    (net (code "89") (name "unconnected-(U1A-PC5-Pad34)") (class "Default")
      (node (ref "U1") (pin "34") (pinfunction "PC5_34") (pintype "bidirectional"))
    )
    (net (code "90") (name "unconnected-(U1A-PC8-Pad65)") (class "Default")
      (node (ref "U1") (pin "65") (pinfunction "PC8_65") (pintype "bidirectional"))
    )
    (net (code "91") (name "unconnected-(U1A-PC9-Pad66)") (class "Default")
      (node (ref "U1") (pin "66") (pinfunction "PC9_66") (pintype "bidirectional"))
    )
    (net (code "92") (name "unconnected-(U1A-PC13-Pad7)") (class "Default")
      (node (ref "U1") (pin "7") (pinfunction "PC13_7") (pintype "bidirectional"))
    )
    (net (code "93") (name "unconnected-(U1A-PC14-OSC32_IN(PC14)-Pad8)") (class "Default")
      (node (ref "U1") (pin "8") (pinfunction "PC14-OSC32_IN(PC14)_8") (pintype "bidirectional"))
    )
    (net (code "94") (name "unconnected-(U1A-PC15-OSC32_OUT(PC15)-Pad9)") (class "Default")
      (node (ref "U1") (pin "9") (pinfunction "PC15-OSC32_OUT(PC15)_9") (pintype "bidirectional"))
    )
    (net (code "95") (name "unconnected-(U1A-PD3-Pad84)") (class "Default")
      (node (ref "U1") (pin "84") (pinfunction "PD3_84") (pintype "bidirectional"))
    )
    (net (code "96") (name "unconnected-(U1A-PD4-Pad85)") (class "Default")
      (node (ref "U1") (pin "85") (pinfunction "PD4_85") (pintype "bidirectional"))
    )
    (net (code "97") (name "unconnected-(U1A-PD7-Pad88)") (class "Default")
      (node (ref "U1") (pin "88") (pinfunction "PD7_88") (pintype "bidirectional"))
    )
    (net (code "98") (name "unconnected-(U1A-PD10-Pad57)") (class "Default")
      (node (ref "U1") (pin "57") (pinfunction "PD10_57") (pintype "bidirectional"))
    )
    (net (code "99") (name "unconnected-(U1A-PD11-Pad58)") (class "Default")
      (node (ref "U1") (pin "58") (pinfunction "PD11_58") (pintype "bidirectional"))
    )
    (net (code "100") (name "unconnected-(U1A-PD14-Pad61)") (class "Default")
      (node (ref "U1") (pin "61") (pinfunction "PD14_61") (pintype "bidirectional"))
    )
    (net (code "101") (name "unconnected-(U1A-PD15-Pad62)") (class "Default")
      (node (ref "U1") (pin "62") (pinfunction "PD15_62") (pintype "bidirectional"))
    )
    (net (code "102") (name "unconnected-(U1A-PE0-Pad97)") (class "Default")
      (node (ref "U1") (pin "97") (pinfunction "PE0_97") (pintype "bidirectional"))
    )
    (net (code "103") (name "unconnected-(U1A-PE1-Pad98)") (class "Default")
      (node (ref "U1") (pin "98") (pinfunction "PE1_98") (pintype "bidirectional"))
    )
    (net (code "104") (name "unconnected-(U1A-PE3-Pad2)") (class "Default")
      (node (ref "U1") (pin "2") (pinfunction "PE3_2") (pintype "bidirectional"))
    )
    (net (code "105") (name "unconnected-(U1A-PE4-Pad3)") (class "Default")
      (node (ref "U1") (pin "3") (pinfunction "PE4_3") (pintype "bidirectional"))
    )
    (net (code "106") (name "unconnected-(U1A-PE5-Pad4)") (class "Default")
      (node (ref "U1") (pin "4") (pinfunction "PE5_4") (pintype "bidirectional"))
    )
    (net (code "107") (name "unconnected-(U1A-PE6-Pad5)") (class "Default")
      (node (ref "U1") (pin "5") (pinfunction "PE6_5") (pintype "bidirectional"))
    )
    (net (code "108") (name "unconnected-(U1A-PE7-Pad38)") (class "Default")
      (node (ref "U1") (pin "38") (pinfunction "PE7_38") (pintype "bidirectional"))
    )
    (net (code "109") (name "unconnected-(U1A-PE8-Pad39)") (class "Default")
      (node (ref "U1") (pin "39") (pinfunction "PE8_39") (pintype "bidirectional"))
    )
    (net (code "110") (name "unconnected-(U1A-PE11-Pad42)") (class "Default")
      (node (ref "U1") (pin "42") (pinfunction "PE11_42") (pintype "bidirectional"))
    )
    (net (code "111") (name "unconnected-(U1A-PE12-Pad43)") (class "Default")
      (node (ref "U1") (pin "43") (pinfunction "PE12_43") (pintype "bidirectional"))
    )
    (net (code "112") (name "unconnected-(U1A-PE15-Pad46)") (class "Default")
      (node (ref "U1") (pin "46") (pinfunction "PE15_46") (pintype "bidirectional"))
    )
    (net (code "113") (name "unconnected-(U2-SHDN-Pad5)") (class "Default")
      (node (ref "U2") (pin "5") (pinfunction "SHDN_5") (pintype "passive+no_connect"))
    )
    (net (code "114") (name "unconnected-(U3-SHDN-Pad5)") (class "Default")
      (node (ref "U3") (pin "5") (pinfunction "SHDN_5") (pintype "passive+no_connect"))
    )
    (net (code "115") (name "unconnected-(U4-CTS-Pad18)") (class "Default")
      (node (ref "U4") (pin "18") (pinfunction "CTS_18") (pintype "passive"))
    )
    (net (code "116") (name "unconnected-(U4-DCD-Pad24)") (class "Default")
      (node (ref "U4") (pin "24") (pinfunction "DCD_24") (pintype "passive"))
    )
    (net (code "117") (name "unconnected-(U4-DSR-Pad22)") (class "Default")
      (node (ref "U4") (pin "22") (pinfunction "DSR_22") (pintype "passive"))
    )
    (net (code "118") (name "unconnected-(U4-DTR-Pad23)") (class "Default")
      (node (ref "U4") (pin "23") (pinfunction "DTR_23") (pintype "passive"))
    )
    (net (code "119") (name "unconnected-(U4-IO0-Pad14)") (class "Default")
      (node (ref "U4") (pin "14") (pinfunction "IO0_14") (pintype "passive"))
    )
    (net (code "120") (name "unconnected-(U4-IO1-Pad13)") (class "Default")
      (node (ref "U4") (pin "13") (pinfunction "IO1_13") (pintype "passive"))
    )
    (net (code "121") (name "unconnected-(U4-IO2-Pad12)") (class "Default")
      (node (ref "U4") (pin "12") (pinfunction "IO2_12") (pintype "passive"))
    )
    (net (code "122") (name "unconnected-(U4-IO3-Pad11)") (class "Default")
      (node (ref "U4") (pin "11") (pinfunction "IO3_11") (pintype "passive"))
    )
    (net (code "123") (name "unconnected-(U4-NC-Pad10)") (class "Default")
      (node (ref "U4") (pin "10") (pinfunction "NC_10") (pintype "passive"))
    )
    (net (code "124") (name "unconnected-(U4-RI-Pad1)") (class "Default")
      (node (ref "U4") (pin "1") (pinfunction "RI_1") (pintype "passive"))
    )
    (net (code "125") (name "unconnected-(U4-RTS-Pad19)") (class "Default")
      (node (ref "U4") (pin "19") (pinfunction "RTS_19") (pintype "passive"))
    )
    (net (code "126") (name "unconnected-(U4-SUSPEND--Pad15)") (class "Default")
      (node (ref "U4") (pin "15") (pinfunction "SUSPEND-_15") (pintype "passive"))
    )
    (net (code "127") (name "unconnected-(U4-SUSPEND-Pad17)") (class "Default")
      (node (ref "U4") (pin "17") (pinfunction "SUSPEND_17") (pintype "passive"))
    )
    (net (code "128") (name "unconnected-(U4-VDD-Pad6)") (class "Default")
      (node (ref "U4") (pin "6") (pinfunction "VDD_6") (pintype "passive"))
    )
  )
)
